# CUSensor.net
KiCad netlist of a schematic drawn in Altium Designer
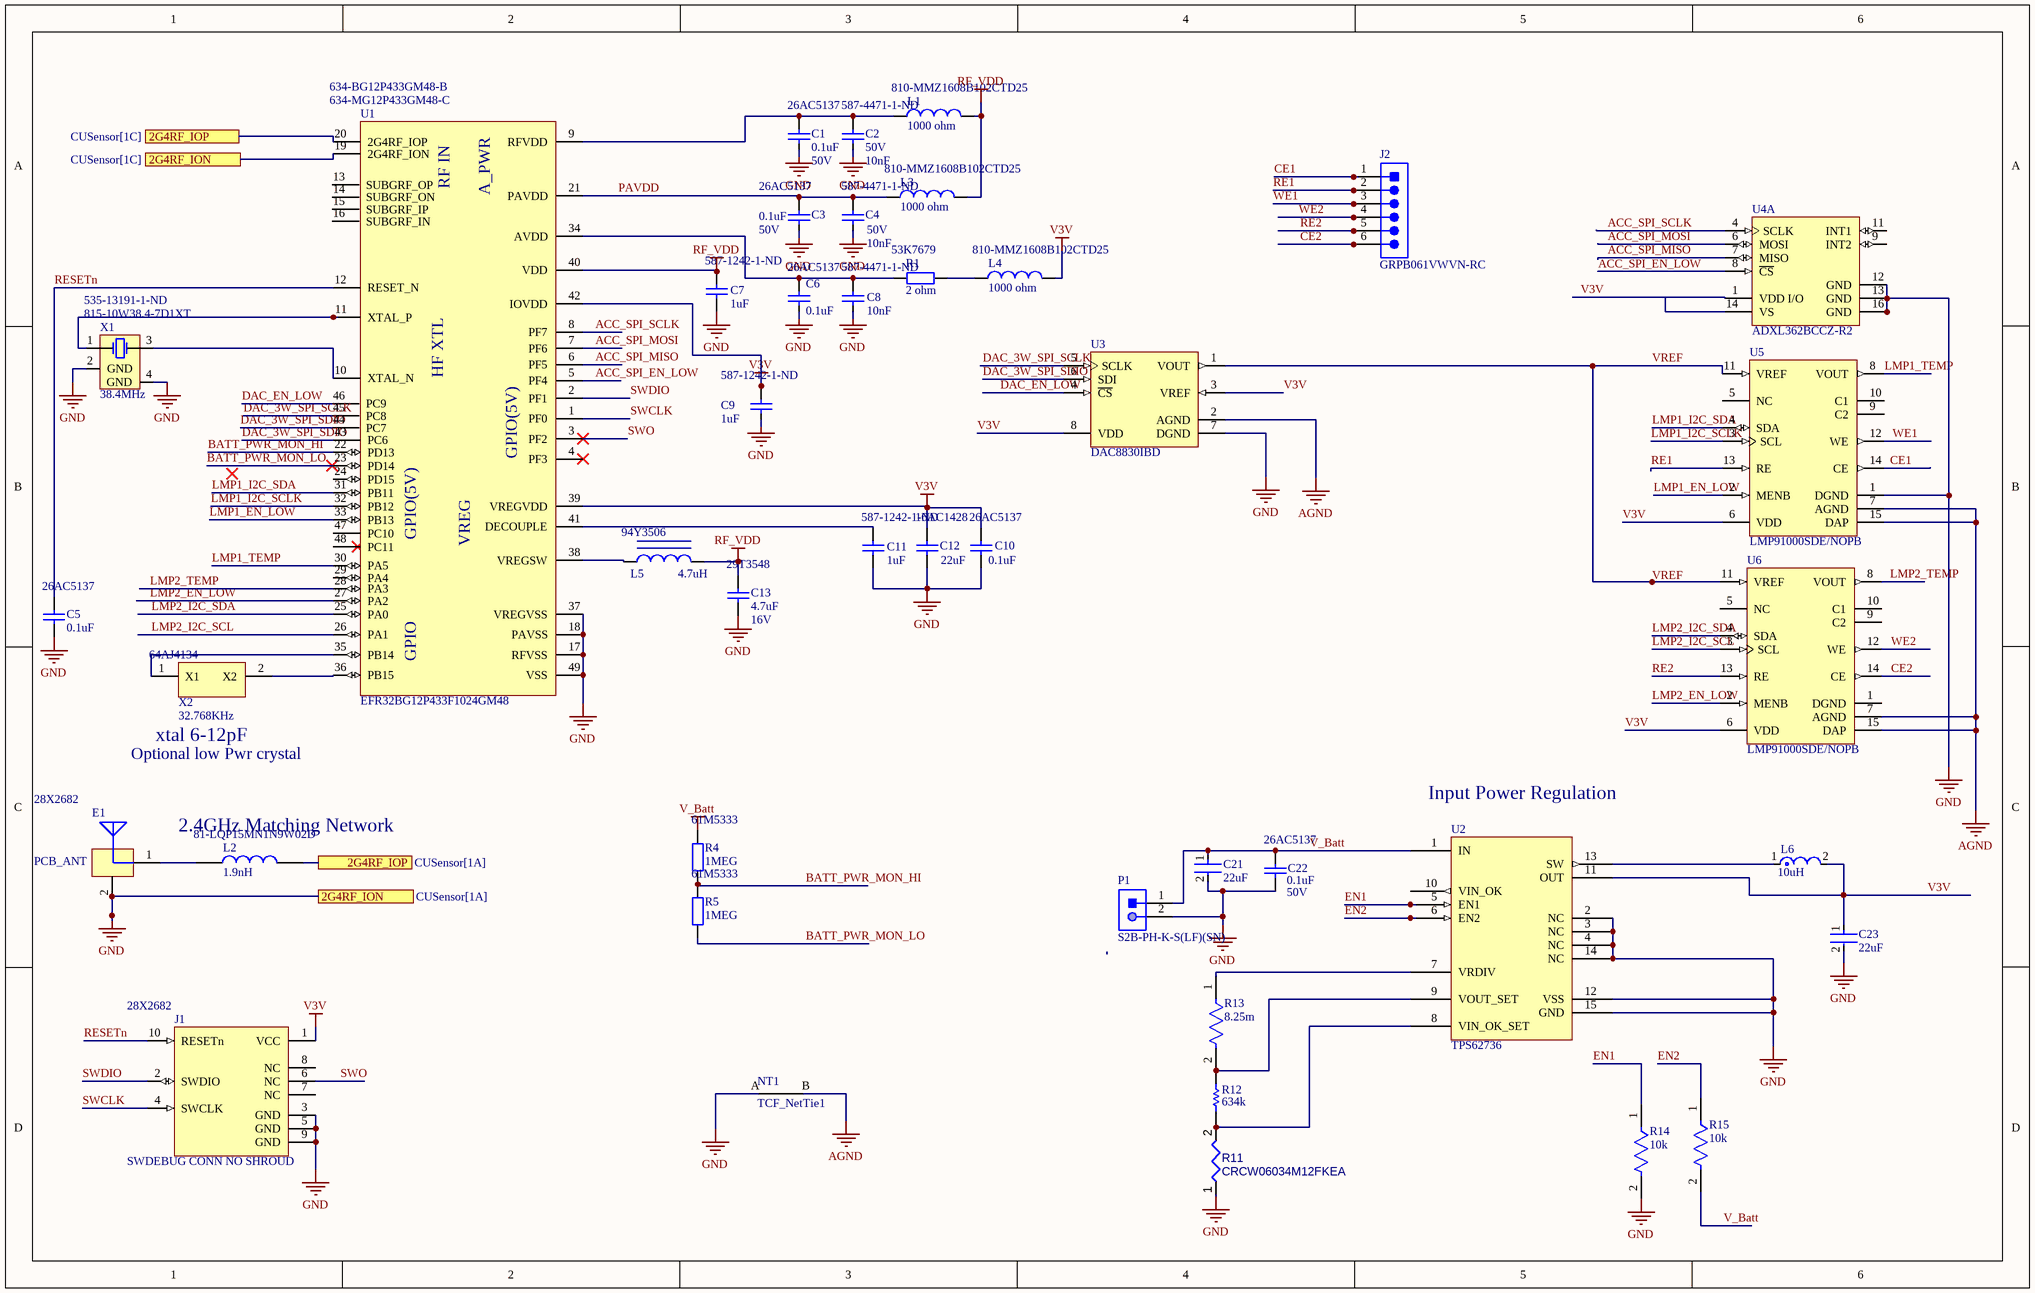
[diagram p0: CUSensor.SchDoc]

(export (version "E")
  (design (tool "Eeschema 10.0.6"))
  (components
    (comp (ref "C1")
      (value "0.1uF")
      (footprint "RESC1608N")
      (description "CAP CER .1UF 50V 10% X7R 0603")
      (fields
        (field (name "MANUFACTURER") "Murata")
        (field (name "MANUFACTURER PART#") "GRM188R71H104KA93D")
        (field (name "VOLTAGE") "50V")
        (field (name "SUPPLIER PART NUMBER 1") "26AC5137")
      )
      (libsource (lib "BCI_SCHEMATIC_LIB") (part "Cap Ceramic 0.1uF 0603_50V"))
    )
    (comp (ref "C2")
      (value "10nF")
      (footprint "RESC1608N")
      (description "CAP CER 10000PF 50V 10% X7R 0603")
      (fields
        (field (name "MANUFACTURER") "Murata")
        (field (name "MANUFACTURER PART#") "GRM188R71H103KA01D")
        (field (name "VOLTAGE") "50V")
        (field (name "SUPPLIER PART NUMBER 1") "587-4471-1-ND")
      )
      (libsource (lib "BCI_SCHEMATIC_LIB") (part "Cap Ceramic 10nF 0603"))
    )
    (comp (ref "C3")
      (value "0.1uF")
      (footprint "RESC1608N")
      (description "CAP CER .1UF 50V 10% X7R 0603")
      (fields
        (field (name "MANUFACTURER") "Murata")
        (field (name "MANUFACTURER PART#") "GRM188R71H104KA93D")
        (field (name "VOLTAGE") "50V")
        (field (name "SUPPLIER PART NUMBER 1") "26AC5137")
      )
      (libsource (lib "BCI_SCHEMATIC_LIB") (part "Cap Ceramic 0.1uF 0603_50V"))
    )
    (comp (ref "C4")
      (value "10nF")
      (footprint "RESC1608N")
      (description "CAP CER 10000PF 50V 10% X7R 0603")
      (fields
        (field (name "MANUFACTURER") "Murata")
        (field (name "MANUFACTURER PART#") "GRM188R71H103KA01D")
        (field (name "VOLTAGE") "50V")
        (field (name "SUPPLIER PART NUMBER 1") "587-4471-1-ND")
      )
      (libsource (lib "BCI_SCHEMATIC_LIB") (part "Cap Ceramic 10nF 0603"))
    )
    (comp (ref "C5")
      (value "0.1uF")
      (footprint "RESC1608N")
      (description "CAP CER .1UF 50V 10% X7R 0603")
      (fields
        (field (name "MANUFACTURER") "Murata")
        (field (name "MANUFACTURER PART#") "GRM188R71H104KA93D")
        (field (name "SUPPLIER PART NUMBER 1") "26AC5137")
      )
      (libsource (lib "BCI_SCHEMATIC_LIB") (part "Cap Ceramic 0.1uF 0603_50V"))
    )
    (comp (ref "C6")
      (value "0.1uF")
      (footprint "RESC1608N")
      (description "CAP CER .1UF 50V 10% X7R 0603")
      (fields
        (field (name "MANUFACTURER") "Murata")
        (field (name "MANUFACTURER PART#") "GRM188R71H104KA93D")
        (field (name "SUPPLIER PART NUMBER 1") "26AC5137")
      )
      (libsource (lib "BCI_SCHEMATIC_LIB") (part "Cap Ceramic 0.1uF 0603_50V"))
    )
    (comp (ref "C7")
      (value "1uF")
      (footprint "RESC1608N")
      (description "CAP CER 1UF 10V 10% X7R 0603")
      (fields
        (field (name "MANUFACTURER") "Taiyo-Yuden")
        (field (name "MANUFACTURER PART#") "LMK107B7105KA-T")
        (field (name "SUPPLIER PART NUMBER 1") "587-1242-1-ND")
      )
      (libsource (lib "BCI_SCHEMATIC_LIB") (part "Cap Ceramic 1uF_10V_ 0603"))
    )
    (comp (ref "C8")
      (value "10nF")
      (footprint "RESC1608N")
      (description "CAP CER 10000PF 50V 10% X7R 0603")
      (fields
        (field (name "MANUFACTURER") "Murata")
        (field (name "MANUFACTURER PART#") "GRM188R71H103KA01D")
        (field (name "SUPPLIER PART NUMBER 1") "587-4471-1-ND")
      )
      (libsource (lib "BCI_SCHEMATIC_LIB") (part "Cap Ceramic 10nF 0603"))
    )
    (comp (ref "C9")
      (value "1uF")
      (footprint "RESC1608N")
      (description "CAP CER 1UF 10V 10% X7R 0603")
      (fields
        (field (name "MANUFACTURER") "Taiyo-Yuden")
        (field (name "MANUFACTURER PART#") "LMK107B7105KA-T")
        (field (name "SUPPLIER PART NUMBER 1") "587-1242-1-ND")
      )
      (libsource (lib "BCI_SCHEMATIC_LIB") (part "Cap Ceramic 1uF_10V_ 0603"))
    )
    (comp (ref "C10")
      (value "0.1uF")
      (footprint "RESC1608N")
      (description "CAP CER .1UF 50V 10% X7R 0603")
      (fields
        (field (name "MANUFACTURER") "Murata")
        (field (name "MANUFACTURER PART#") "GRM188R71H104KA93D")
        (field (name "SUPPLIER PART NUMBER 1") "26AC5137")
      )
      (libsource (lib "BCI_SCHEMATIC_LIB") (part "Cap Ceramic 0.1uF 0603_50V"))
    )
    (comp (ref "C11")
      (value "1uF")
      (footprint "RESC1608N")
      (description "CAP CER 1UF 10V 10% X7R 0603")
      (fields
        (field (name "MANUFACTURER") "Taiyo-Yuden")
        (field (name "MANUFACTURER PART#") "LMK107B7105KA-T")
        (field (name "SUPPLIER PART NUMBER 1") "587-1242-1-ND")
      )
      (libsource (lib "BCI_SCHEMATIC_LIB") (part "Cap Ceramic 1uF_10V_ 0603"))
    )
    (comp (ref "C12")
      (value "22uF")
      (footprint "RESC1608N")
      (description "CAP CER 22UF 6.3V 20% X5R 0603")
      (fields
        (field (name "MANUFACTURER") "Samsung Electro-Mechanics America")
        (field (name "MANUFACTURER PART#") "CL10A226MQ8NRNE")
        (field (name "SUPPLIER PART NUMBER 1") "16AC1428")
      )
      (libsource (lib "BCI_SCHEMATIC_LIB") (part "Cap Ceramic 22uF 0603 6.3V"))
    )
    (comp (ref "C13")
      (value "4.7uF")
      (footprint "RESC1608N")
      (description "CAP CER 4.7UF 16V 10% X5R 0603")
      (fields
        (field (name "MANUFACTURER") "Taiyo Yuden")
        (field (name "MANUFACTURER PART#") "EMK107ABJ475KA-T")
        (field (name "VOLTAGE") "16V")
        (field (name "SUPPLIER PART NUMBER 1") "29T3548")
      )
      (libsource (lib "BCI_SCHEMATIC_LIB") (part "Cap Ceramic 4.7UF 16V 0603"))
    )
    (comp (ref "C21")
      (value "22uF")
      (footprint "FP-GCJ31C-0_3-IPC_B")
      (description "Cap Ceramic 22uF 10V X7R 10% Pad SMD 1206 Soft Termination  +125°C Automotive T/R")
      (libsource (lib "Altium Content Vault") (part "b4654b650e69147ec39a6b967a45e02"))
    )
    (comp (ref "C22")
      (value "0.1uF")
      (footprint "RESC1608N")
      (description "CAP CER .1UF 50V 10% X7R 0603")
      (fields
        (field (name "MANUFACTURER") "Murata")
        (field (name "MANUFACTURER PART#") "GRM188R71H104KA93D")
        (field (name "VOLTAGE") "50V")
        (field (name "SUPPLIER PART NUMBER 1") "26AC5137")
      )
      (libsource (lib "BCI_SCHEMATIC_LIB") (part "Cap Ceramic 0.1uF 0603_50V"))
    )
    (comp (ref "C23")
      (value "22uF")
      (footprint "FP-GCJ31C-0_3-IPC_B")
      (description "Cap Ceramic 22uF 10V X7R 10% Pad SMD 1206 Soft Termination  +125°C Automotive T/R")
      (libsource (lib "Altium Content Vault") (part "b4654b650e69147ec39a6b967a45e02"))
    )
    (comp (ref "E1")
      (value "PCB_ANT")
      (footprint "PCB_ANT_2.4GHz CIRCULAR")
      (description "Antenna 2.4GHz_PCB Printed")
      (fields (field (name "SUPPLIER PART NUMBER 1") "28X2682"))
      (libsource (lib "BCI_SCHEMATIC_LIB") (part "Antenna_2.4GHZ_Printed_Copper_Circular"))
    )
    (comp (ref "J1")
      (value "SWDEBUG CONN NO SHROUD")
      (footprint "CONN SMT 10 pin Dual Row - 0.050\" FCI shroudless")
      (description "CONN HEADER 10POS DL UNSHRD SMD")
      (fields
        (field (name "MANUFACTURER") "FCI")
        (field (name "DIGIKEY PART#") "609-3695-1-ND")
        (field (name "SUPPLIER PART NUMBER 1") "28X2682")
      )
      (libsource (lib "BCI_SCHEMATIC_LIB") (part "CONN JTAG SMT NO SHROUD NXP"))
    )
    (comp (ref "J2")
      (value "GRPB061VWVN-RC")
      (footprint "SLIN-GRPB061VWVN-RC_V")
      (fields (field (name "MANUFACTURER") "Sullins"))
      (libsource (lib "Altium Content Vault") (part "CN-1P-M-R6"))
    )
    (comp (ref "L1")
      (value "1000 ohm")
      (footprint "RESC1608N")
      (description "FERRITE CHIP 1000 OHM 300MA 0603")
      (fields
        (field (name "DIGIKEY PART#") "445-8672-1-ND")
        (field (name "MANUFACTURER") "TDK")
        (field (name "SUPPLIER PART NUMBER 1") "810-MMZ1608B102CTD25")
      )
      (libsource (lib "BCI_SCHEMATIC_LIB") (part "Ind Filter 0.3A_0603"))
    )
    (comp (ref "L2")
      (value "1.9nH")
      (footprint "RESC1005N")
      (fields
        (field (name "DIGIKEY PART#") "490-11739-6-ND")
        (field (name "MANUFACTURER") "Murata")
        (field (name "MANUFACTURER PART#") "LQP15MN1N9W02D")
        (field (name "SUPPLIER PART NUMBER 1") "81-LQP15MN1N9W02D")
      )
      (libsource (lib "BCI_SCHEMATIC_LIB") (part "Ind Signal 1.9nH 220mA 300mohm 0402"))
    )
    (comp (ref "L3")
      (value "1000 ohm")
      (footprint "RESC1608N")
      (description "FERRITE CHIP 1000 OHM 300MA 0603")
      (fields
        (field (name "DIGIKEY PART#") "445-8672-1-ND")
        (field (name "MANUFACTURER") "TDK")
        (field (name "SUPPLIER PART NUMBER 1") "810-MMZ1608B102CTD25")
      )
      (libsource (lib "BCI_SCHEMATIC_LIB") (part "Ind Filter 0.3A_0603"))
    )
    (comp (ref "L4")
      (value "1000 ohm")
      (footprint "RESC1608N")
      (description "FERRITE CHIP 1000 OHM 300MA 0603")
      (fields
        (field (name "DIGIKEY PART#") "445-8672-1-ND")
        (field (name "MANUFACTURER") "TDK")
        (field (name "SUPPLIER PART NUMBER 1") "810-MMZ1608B102CTD25")
      )
      (libsource (lib "BCI_SCHEMATIC_LIB") (part "Ind Filter 0.3A_0603"))
    )
    (comp (ref "L5")
      (value "4.7uH")
      (footprint "RESC2016N")
      (description "FIXED IND 4.7UH 900MA 360 MOHM")
      (fields
        (field (name "MANUFACTURER") "Bourns")
        (field (name "MANUFACTURER PART#") "SRN2010TA-4R7M")
        (field (name "SUPPLIER PART NUMBER 1") "94Y3506")
      )
      (libsource (lib "BCI_SCHEMATIC_LIB") (part "IND PWR 4.7uH 900mA 360mohm 0806"))
    )
    (comp (ref "L6")
      (value "10uH")
      (footprint "FP-LPS4018-MFG")
      (description "Shielded Power Inductors")
      (fields (field (name "TOLERANCE") "20%"))
      (libsource (lib "Altium Content Vault") (part "4cc4b267dca4c8e51f7102f422741d8"))
    )
    (comp (ref "NT1")
      (value "TCF_NetTie1")
      (footprint "TCF_NetTie1-Footprint-1")
      (description "A Net Tie")
      (libsource (lib "Altium Concord Pro on Altium 365") (part "NetTie"))
    )
    (comp (ref "P1")
      (value "S2B-PH-K-S(LF)(SN)")
      (footprint "JST-S2B-PH-K-S_V")
      (fields (field (name "TOLERANCE") "20%"))
      (libsource (lib "Altium Content Vault") (part "CN-1P-M-R2"))
    )
    (comp (ref "R1")
      (value "2 ohm")
      (footprint "RESC1608N")
      (description "RES SMD 2 OHM 1% 1/10W 0603")
      (fields
        (field (name "DIGIKEY PART#") "1276-4476-1-ND")
        (field (name "MANUFACTURER") "Samsung")
        (field (name "SUPPLIER PART NUMBER 1") "53K7679")
      )
      (libsource (lib "BCI_SCHEMATIC_LIB") (part "RES SMT 2 ohm  1% 0603"))
    )
    (comp (ref "R4")
      (value "1MEG")
      (footprint "RESC1608N")
      (description "RES SMD 1M OHM 1% 1/10W 0603")
      (fields
        (field (name "DIGIKEY PART#") "P1.00MHTR-ND")
        (field (name "MANUFACTURER") "Panasonic")
        (field (name "SUPPLIER PART NUMBER 1") "61M5333")
      )
      (libsource (lib "BCI_SCHEMATIC_LIB") (part "RES SMT 1MEG 1% 0603"))
    )
    (comp (ref "R5")
      (value "1MEG")
      (footprint "RESC1608N")
      (description "RES SMD 1M OHM 1% 1/10W 0603")
      (fields
        (field (name "DIGIKEY PART#") "P1.00MHTR-ND")
        (field (name "MANUFACTURER") "Panasonic")
        (field (name "SUPPLIER PART NUMBER 1") "61M5333")
      )
      (libsource (lib "BCI_SCHEMATIC_LIB") (part "RES SMT 1MEG 1% 0603"))
    )
    (comp (ref "R11")
      (value "CRCW06034M12FKEA")
      (footprint "RESC1608X05N")
      (description "Res Thick Film 0603 4.12M Ohm 1% 1/10W ±100ppm/°C Molded SMD SMD Paper T/R")
      (fields (field (name "MANUFACTURER") "Vishay"))
      (libsource (lib "Altium Concord Pro on Altium 365") (part "44D2KR2F"))
    )
    (comp (ref "R12")
      (value "634k")
      (footprint "RESC1609X50X30LL10T20")
      (fields (field (name "PART NUMBER") "CRCW0603634KFKEA") (field (name "MANUFACTURER") "Vishay Dale"))
      (libsource (lib "Altium Content Vault") (part "RES"))
    )
    (comp (ref "R13")
      (value "8.25m")
      (footprint "FP-CRCW0603-e3-IPC_B")
      (description "RES Thick Film, 8.25MΩ, 1%, 0.1W, 100ppm/°C, 0603")
      (fields (field (name "TOLERANCE") "1%"))
      (libsource (lib "Altium Content Vault") (part "1029c3af85768c4190bb7ad29bc67b5"))
    )
    (comp (ref "R14")
      (value "10k")
      (footprint "FP-RT0603-MFG")
      (description "RES SMD 10K OHM 0.1% 1/10W 0603")
      (fields
        (field (name "TOLERANCE") "0.001")
        (field (name "OCTOPART") "https://octopart.com/rt0603bre0710kl-yageo-1273959")
      )
      (libsource (lib "Altium Content Vault") (part "1029c3af85768c4190bb7ad29bc67b5"))
    )
    (comp (ref "R15")
      (value "10k")
      (footprint "FP-RT0603-MFG")
      (description "RES SMD 10K OHM 0.1% 1/10W 0603")
      (fields
        (field (name "TOLERANCE") "0.001")
        (field (name "OCTOPART") "https://octopart.com/rt0603bre0710kl-yageo-1273959")
      )
      (libsource (lib "Altium Content Vault") (part "1029c3af85768c4190bb7ad29bc67b5"))
    )
    (comp (ref "U1")
      (value "EFR32BG12P433F1024GM48")
      (footprint "QFN50P700X700X90_HS-49N")
      (fields
        (field (name "SUPPLIER PART NUMBER 1") "634-MG12P433GM48-C")
        (field (name "SUPPLIER PART NUMBER 2") "634-BG12P433GM48-B")
      )
      (libsource (lib "EFR32MG Series 1 BLE SubGhz QFN48") (part "EFR32BG12P433F1024GM48"))
    )
    (comp (ref "U2")
      (value "TPS62736")
      (footprint "QFN127P600-8N")
      (description "High Efficiency Nanopower Buck Converter with 50mA Load Capability")
      (libsource (lib "Altium Concord Pro on Altium 365") (part "TPS62736-Symbol-1"))
    )
    (comp (ref "U3")
      (value "DAC8830IBD")
      (footprint "TI-D8_M")
      (fields (field (name "MANUFACTURER") "Texas Instruments"))
      (libsource (lib "Altium Content Vault") (part "TI-DAC8830_EP-D8"))
    )
    (comp (ref "U4")
      (value "ADXL362BCCZ-R2")
      (footprint "ADI-CC-16-4_M")
      (fields (field (name "MANUFACTURER") "Analog Devices"))
      (libsource (lib "Altium Content Vault") (part "ADI-ADXL362-CC-16-4"))
    )
    (comp (ref "U5")
      (value "LMP91000SDE/NOPB")
      (footprint "NHL0014B_V")
      (description "Configurable AFE Potentiostat for Low-Power Chemical Sensing Applications, 14-pin LLP, 250 Reel")
      (fields (field (name "MANUFACTURER") "Texas Instruments"))
      (libsource (lib "Altium Content Vault") (part "SEN-ELECHEM-LMP91000-15"))
    )
    (comp (ref "U6")
      (value "LMP91000SDE/NOPB")
      (footprint "NHL0014B_V")
      (description "Configurable AFE Potentiostat for Low-Power Chemical Sensing Applications, 14-pin LLP, 250 Reel")
      (fields (field (name "MANUFACTURER") "Texas Instruments"))
      (libsource (lib "Altium Content Vault") (part "SEN-ELECHEM-LMP91000-15"))
    )
    (comp (ref "X1")
      (value "38.4MHz")
      (footprint "CRYSTAL SMD 2.5x2.0 ABRACON")
      (description "CRYSTAL 38.4MHZ 7pF")
      (fields
        (field (name "MANUFACTURER") "Abracon")
        (field (name "DIGIKEY PART#") "535-13784-2-ND")
        (field (name "SUPPLIER PART NUMBER 1") "815-10W38.4-7D1XT")
        (field (name "SUPPLIER PART NUMBER 2") "535-13191-1-ND")
      )
      (libsource (lib "BCI_SCHEMATIC_LIB") (part "CRYSTAL 38.4MHZ 7PF_SMD_2.5mmx2mm"))
    )
    (comp (ref "X2")
      (value "32.768KHz")
      (footprint "Crystal_SMD_3.2x1.5mm")
      (description "CRYSTAL 32.7680KHZ 12.5PF SMD")
      (fields
        (field (name "MANUFACTURER") "ECS")
        (field (name "DIGIKEY PART#") "XC1617TR-ND")
        (field (name "SUPPLIER PART NUMBER 1") "64AJ4134")
      )
      (libsource (lib "BCI_SCHEMATIC_LIB") (part "Crystal_32.768KHz 12.5pF SMD 3.2x1.5mm ECS ECS-.327-12.5-34B-TR"))
    )
  )
  (nets
    (net (code "1") (name "/2G4RF_IOP") (class "Default")
      (node (ref "L2") (pin "2") (pinfunction "2_2") (pintype "passive"))
      (node (ref "U1") (pin "20") (pinfunction "2G4RF_IOP_20") (pintype "passive"))
    )
    (net (code "2") (name "/ACC_SPI_EN_LOW") (class "Default")
      (node (ref "U1") (pin "5") (pinfunction "PF4_5") (pintype "passive"))
      (node (ref "U4") (pin "8") (pinfunction "~{CS}_8") (pintype "input"))
    )
    (net (code "3") (name "/ACC_SPI_MISO") (class "Default")
      (node (ref "U1") (pin "6") (pinfunction "PF5_6") (pintype "passive"))
      (node (ref "U4") (pin "7") (pinfunction "MISO_7") (pintype "bidirectional"))
    )
    (net (code "4") (name "/ACC_SPI_MOSI") (class "Default")
      (node (ref "U1") (pin "7") (pinfunction "PF6_7") (pintype "passive"))
      (node (ref "U4") (pin "6") (pinfunction "MOSI_6") (pintype "bidirectional"))
    )
    (net (code "5") (name "/ACC_SPI_SCLK") (class "Default")
      (node (ref "U1") (pin "8") (pinfunction "PF7_8") (pintype "passive"))
      (node (ref "U4") (pin "4") (pinfunction "SCLK_4") (pintype "input"))
    )
    (net (code "6") (name "/BATT_PWR_MON_HI") (class "Default")
      (node (ref "R4") (pin "1") (pintype "power_in"))
      (node (ref "R5") (pin "2") (pintype "power_in"))
      (node (ref "U1") (pin "22") (pinfunction "PD13_22") (pintype "bidirectional"))
    )
    (net (code "7") (name "/BATT_PWR_MON_LO") (class "Default")
      (node (ref "R5") (pin "1") (pintype "power_in"))
      (node (ref "U1") (pin "23") (pinfunction "PD14_23") (pintype "bidirectional"))
    )
    (net (code "8") (name "/CE1") (class "Default")
      (node (ref "J2") (pin "1") (pinfunction "1_1") (pintype "passive"))
      (node (ref "U5") (pin "14") (pinfunction "CE_14") (pintype "output"))
    )
    (net (code "9") (name "/CE2") (class "Default")
      (node (ref "J2") (pin "6") (pinfunction "6_6") (pintype "passive"))
      (node (ref "U6") (pin "14") (pinfunction "CE_14") (pintype "output"))
    )
    (net (code "10") (name "/DAC_3W_SPI_SCLK") (class "Default")
      (node (ref "U1") (pin "45") (pinfunction "PC8_45") (pintype "power_in"))
      (node (ref "U3") (pin "5") (pinfunction "SCLK_5") (pintype "input"))
    )
    (net (code "11") (name "/DAC_3W_SPI_SDIO") (class "Default")
      (node (ref "U1") (pin "43") (pinfunction "PC6_43") (pintype "power_in"))
      (node (ref "U1") (pin "44") (pinfunction "PC7_44") (pintype "power_in"))
      (node (ref "U3") (pin "6") (pinfunction "SDI_6") (pintype "input"))
    )
    (net (code "12") (name "/DAC_EN_LOW") (class "Default")
      (node (ref "U1") (pin "46") (pinfunction "PC9_46") (pintype "power_in"))
      (node (ref "U3") (pin "4") (pinfunction "~{CS}_4") (pintype "input"))
    )
    (net (code "13") (name "/EN1") (class "Default")
      (node (ref "R14") (pin "1") (pinfunction "1_1") (pintype "passive"))
      (node (ref "U2") (pin "5") (pinfunction "EN1_5") (pintype "input"))
    )
    (net (code "14") (name "/EN2") (class "Default")
      (node (ref "R15") (pin "1") (pinfunction "1_1") (pintype "passive"))
      (node (ref "U2") (pin "6") (pinfunction "EN2_6") (pintype "input"))
    )
    (net (code "15") (name "/LMP1_EN_LOW") (class "Default")
      (node (ref "U1") (pin "33") (pinfunction "PB13_33") (pintype "bidirectional"))
      (node (ref "U5") (pin "2") (pinfunction "MENB_2") (pintype "input"))
    )
    (net (code "16") (name "/LMP1_I2C_SCLK") (class "Default")
      (node (ref "U1") (pin "32") (pinfunction "PB12_32") (pintype "bidirectional"))
      (node (ref "U5") (pin "3") (pinfunction "SCL_3") (pintype "input"))
    )
    (net (code "17") (name "/LMP1_I2C_SDA") (class "Default")
      (node (ref "U1") (pin "31") (pinfunction "PB11_31") (pintype "bidirectional"))
      (node (ref "U5") (pin "4") (pinfunction "SDA_4") (pintype "bidirectional"))
    )
    (net (code "18") (name "/LMP1_TEMP") (class "Default")
      (node (ref "U1") (pin "30") (pinfunction "PA5_30") (pintype "bidirectional"))
      (node (ref "U5") (pin "8") (pinfunction "VOUT_8") (pintype "output"))
    )
    (net (code "19") (name "/LMP2_EN_LOW") (class "Default")
      (node (ref "U1") (pin "27") (pinfunction "PA2_27") (pintype "bidirectional"))
      (node (ref "U6") (pin "2") (pinfunction "MENB_2") (pintype "input"))
    )
    (net (code "20") (name "/LMP2_I2C_SCL") (class "Default")
      (node (ref "U1") (pin "26") (pinfunction "PA1_26") (pintype "bidirectional"))
      (node (ref "U6") (pin "3") (pinfunction "SCL_3") (pintype "input"))
    )
    (net (code "21") (name "/LMP2_I2C_SDA") (class "Default")
      (node (ref "U1") (pin "25") (pinfunction "PA0_25") (pintype "bidirectional"))
      (node (ref "U6") (pin "4") (pinfunction "SDA_4") (pintype "bidirectional"))
    )
    (net (code "22") (name "/LMP2_TEMP") (class "Default")
      (node (ref "U1") (pin "28") (pinfunction "PA3_28") (pintype "bidirectional"))
      (node (ref "U6") (pin "8") (pinfunction "VOUT_8") (pintype "output"))
    )
    (net (code "23") (name "/PAVDD") (class "Default")
      (node (ref "C3") (pin "2") (pinfunction "2_2") (pintype "passive"))
      (node (ref "C4") (pin "2") (pinfunction "2_2") (pintype "passive"))
      (node (ref "L3") (pin "1") (pinfunction "1_1") (pintype "passive"))
      (node (ref "U1") (pin "21") (pinfunction "PAVDD_21") (pintype "passive"))
    )
    (net (code "24") (name "/RE1") (class "Default")
      (node (ref "J2") (pin "2") (pinfunction "2_2") (pintype "passive"))
      (node (ref "U5") (pin "13") (pinfunction "RE_13") (pintype "input"))
    )
    (net (code "25") (name "/RE2") (class "Default")
      (node (ref "J2") (pin "5") (pinfunction "5_5") (pintype "passive"))
      (node (ref "U6") (pin "13") (pinfunction "RE_13") (pintype "input"))
    )
    (net (code "26") (name "/RESETn") (class "Default")
      (node (ref "C5") (pin "1") (pinfunction "1_1") (pintype "passive"))
      (node (ref "J1") (pin "10") (pinfunction "RESETn_10") (pintype "input"))
      (node (ref "U1") (pin "12") (pinfunction "RESET_N_12") (pintype "passive"))
    )
    (net (code "27") (name "/SWCLK") (class "Default")
      (node (ref "J1") (pin "4") (pinfunction "SWCLK_4") (pintype "input"))
      (node (ref "U1") (pin "1") (pinfunction "PF0_1") (pintype "passive"))
    )
    (net (code "28") (name "/SWDIO") (class "Default")
      (node (ref "J1") (pin "2") (pinfunction "SWDIO_2") (pintype "bidirectional"))
      (node (ref "U1") (pin "2") (pinfunction "PF1_2") (pintype "passive"))
    )
    (net (code "29") (name "/SWO") (class "Default")
      (node (ref "J1") (pin "6") (pinfunction "NC_6") (pintype "passive"))
      (node (ref "U1") (pin "3") (pinfunction "PF2_3") (pintype "passive"))
    )
    (net (code "30") (name "/VREF") (class "Default")
      (node (ref "U3") (pin "1") (pinfunction "VOUT_1") (pintype "output"))
      (node (ref "U5") (pin "11") (pinfunction "VREF_11") (pintype "input"))
      (node (ref "U6") (pin "11") (pinfunction "VREF_11") (pintype "input"))
    )
    (net (code "31") (name "/WE1") (class "Default")
      (node (ref "J2") (pin "3") (pinfunction "3_3") (pintype "passive"))
      (node (ref "U5") (pin "12") (pinfunction "WE_12") (pintype "output"))
    )
    (net (code "32") (name "/WE2") (class "Default")
      (node (ref "J2") (pin "4") (pinfunction "4_4") (pintype "passive"))
      (node (ref "U6") (pin "12") (pinfunction "WE_12") (pintype "output"))
    )
    (net (code "33") (name "AGND") (class "Default")
      (node (ref "NT1") (pin "B") (pinfunction "B_B") (pintype "passive"))
      (node (ref "U3") (pin "2") (pinfunction "AGND_2") (pintype "power_in"))
      (node (ref "U5") (pin "15") (pinfunction "DAP_15") (pintype "power_in"))
      (node (ref "U5") (pin "7") (pinfunction "AGND_7") (pintype "power_in"))
      (node (ref "U6") (pin "15") (pinfunction "DAP_15") (pintype "power_in"))
      (node (ref "U6") (pin "7") (pinfunction "AGND_7") (pintype "power_in"))
    )
    (net (code "34") (name "GND") (class "Default")
      (node (ref "C1") (pin "1") (pinfunction "1_1") (pintype "passive"))
      (node (ref "C10") (pin "1") (pinfunction "1_1") (pintype "passive"))
      (node (ref "C11") (pin "1") (pinfunction "1_1") (pintype "passive"))
      (node (ref "C12") (pin "1") (pinfunction "1_1") (pintype "passive"))
      (node (ref "C13") (pin "1") (pinfunction "1_1") (pintype "passive"))
      (node (ref "C2") (pin "1") (pinfunction "1_1") (pintype "passive"))
      (node (ref "C21") (pin "2") (pinfunction "2_2") (pintype "passive"))
      (node (ref "C22") (pin "1") (pinfunction "1_1") (pintype "passive"))
      (node (ref "C23") (pin "2") (pinfunction "2_2") (pintype "passive"))
      (node (ref "C3") (pin "1") (pinfunction "1_1") (pintype "passive"))
      (node (ref "C4") (pin "1") (pinfunction "1_1") (pintype "passive"))
      (node (ref "C5") (pin "2") (pinfunction "2_2") (pintype "passive"))
      (node (ref "C6") (pin "1") (pinfunction "1_1") (pintype "passive"))
      (node (ref "C7") (pin "1") (pinfunction "1_1") (pintype "passive"))
      (node (ref "C8") (pin "1") (pinfunction "1_1") (pintype "passive"))
      (node (ref "C9") (pin "1") (pinfunction "1_1") (pintype "passive"))
      (node (ref "E1") (pin "2") (pinfunction "GND_2") (pintype "passive"))
      (node (ref "J1") (pin "3") (pinfunction "GND_3") (pintype "passive"))
      (node (ref "J1") (pin "5") (pinfunction "GND_5") (pintype "passive"))
      (node (ref "J1") (pin "9") (pinfunction "GND_9") (pintype "passive"))
      (node (ref "NT1") (pin "A") (pinfunction "A_A") (pintype "passive"))
      (node (ref "P1") (pin "2") (pinfunction "2_2") (pintype "passive"))
      (node (ref "R11") (pin "1") (pinfunction "1_1") (pintype "passive"))
      (node (ref "R14") (pin "2") (pinfunction "2_2") (pintype "passive"))
      (node (ref "U1") (pin "17") (pinfunction "RFVSS_17") (pintype "passive"))
      (node (ref "U1") (pin "18") (pinfunction "PAVSS_18") (pintype "power_in"))
      (node (ref "U1") (pin "19") (pinfunction "2G4RF_ION_19") (pintype "passive"))
      (node (ref "U1") (pin "37") (pinfunction "VREGVSS_37") (pintype "power_in"))
      (node (ref "U1") (pin "49") (pinfunction "VSS_49") (pintype "passive"))
      (node (ref "U2") (pin "12") (pinfunction "VSS_12") (pintype "power_in"))
      (node (ref "U2") (pin "14") (pinfunction "NC_14") (pintype "passive"))
      (node (ref "U2") (pin "15") (pinfunction "GND_15") (pintype "power_in"))
      (node (ref "U2") (pin "2") (pinfunction "NC_2") (pintype "passive"))
      (node (ref "U2") (pin "3") (pinfunction "NC_3") (pintype "passive"))
      (node (ref "U2") (pin "4") (pinfunction "NC_4") (pintype "passive"))
      (node (ref "U3") (pin "7") (pinfunction "DGND_7") (pintype "power_in"))
      (node (ref "U4") (pin "12") (pinfunction "GND_12") (pintype "power_in"))
      (node (ref "U4") (pin "13") (pinfunction "GND_13") (pintype "power_in"))
      (node (ref "U4") (pin "16") (pinfunction "GND_16") (pintype "power_in"))
      (node (ref "U5") (pin "1") (pinfunction "DGND_1") (pintype "power_in"))
      (node (ref "X1") (pin "2") (pinfunction "GND_2") (pintype "passive"))
      (node (ref "X1") (pin "4") (pinfunction "GND_4") (pintype "passive"))
    )
    (net (code "35") (name "Net-(E1-SIG)") (class "Default")
      (node (ref "E1") (pin "1") (pinfunction "SIG_1") (pintype "passive"))
      (node (ref "L2") (pin "1") (pinfunction "1_1") (pintype "passive"))
    )
    (net (code "36") (name "Net-(L4-Pad1)") (class "Default")
      (node (ref "L4") (pin "1") (pinfunction "1_1") (pintype "passive"))
      (node (ref "R1") (pin "2") (pintype "power_in"))
    )
    (net (code "37") (name "Net-(U1-AVDD)") (class "Default")
      (node (ref "C6") (pin "2") (pinfunction "2_2") (pintype "passive"))
      (node (ref "C8") (pin "2") (pinfunction "2_2") (pintype "passive"))
      (node (ref "R1") (pin "1") (pintype "power_in"))
      (node (ref "U1") (pin "34") (pinfunction "AVDD_34") (pintype "power_in"))
    )
    (net (code "38") (name "Net-(U1-DECOUPLE)") (class "Default")
      (node (ref "C11") (pin "2") (pinfunction "2_2") (pintype "passive"))
      (node (ref "U1") (pin "41") (pinfunction "DECOUPLE_41") (pintype "power_in"))
    )
    (net (code "39") (name "Net-(U1-PB14)") (class "Default")
      (node (ref "U1") (pin "35") (pinfunction "PB14_35") (pintype "bidirectional"))
      (node (ref "X2") (pin "1") (pinfunction "X1_1") (pintype "passive"))
    )
    (net (code "40") (name "Net-(U1-PB15)") (class "Default")
      (node (ref "U1") (pin "36") (pinfunction "PB15_36") (pintype "bidirectional"))
      (node (ref "X2") (pin "2") (pinfunction "X2_2") (pintype "passive"))
    )
    (net (code "41") (name "Net-(U1-RFVDD)") (class "Default")
      (node (ref "C1") (pin "2") (pinfunction "2_2") (pintype "passive"))
      (node (ref "C2") (pin "2") (pinfunction "2_2") (pintype "passive"))
      (node (ref "L1") (pin "1") (pinfunction "1_1") (pintype "passive"))
      (node (ref "U1") (pin "9") (pinfunction "RFVDD_9") (pintype "passive"))
    )
    (net (code "42") (name "Net-(U1-VREGSW)") (class "Default")
      (node (ref "L5") (pin "1") (pinfunction "1_1") (pintype "passive"))
      (node (ref "U1") (pin "38") (pinfunction "VREGSW_38") (pintype "power_in"))
    )
    (net (code "43") (name "Net-(U1-XTAL_N)") (class "Default")
      (node (ref "U1") (pin "10") (pinfunction "XTAL_N_10") (pintype "passive"))
      (node (ref "X1") (pin "3") (pinfunction "OSC2_3") (pintype "passive"))
    )
    (net (code "44") (name "Net-(U1-XTAL_P)") (class "Default")
      (node (ref "U1") (pin "11") (pinfunction "XTAL_P_11") (pintype "passive"))
      (node (ref "X1") (pin "1") (pinfunction "OSC1_1") (pintype "passive"))
    )
    (net (code "45") (name "Net-(U2-SW)") (class "Default")
      (node (ref "L6") (pin "1") (pinfunction "1_1") (pintype "passive"))
      (node (ref "U2") (pin "13") (pinfunction "SW_13") (pintype "output"))
    )
    (net (code "46") (name "Net-(U2-VIN_OK_SET)") (class "Default")
      (node (ref "R11") (pin "2") (pinfunction "2_2") (pintype "passive"))
      (node (ref "R12") (pin "1") (pinfunction "1_1") (pintype "passive"))
      (node (ref "U2") (pin "8") (pinfunction "VIN_OK_SET_8") (pintype "passive"))
    )
    (net (code "47") (name "Net-(U2-VOUT_SET)") (class "Default")
      (node (ref "R12") (pin "2") (pinfunction "2_2") (pintype "passive"))
      (node (ref "R13") (pin "2") (pinfunction "2_2") (pintype "passive"))
      (node (ref "U2") (pin "9") (pinfunction "VOUT_SET_9") (pintype "passive"))
    )
    (net (code "48") (name "Net-(U2-VRDIV)") (class "Default")
      (node (ref "R13") (pin "1") (pinfunction "1_1") (pintype "passive"))
      (node (ref "U2") (pin "7") (pinfunction "VRDIV_7") (pintype "passive"))
    )
    (net (code "49") (name "RF_VDD") (class "Default")
      (node (ref "C13") (pin "2") (pinfunction "2_2") (pintype "passive"))
      (node (ref "C7") (pin "2") (pinfunction "2_2") (pintype "passive"))
      (node (ref "L1") (pin "2") (pinfunction "2_2") (pintype "passive"))
      (node (ref "L3") (pin "2") (pinfunction "2_2") (pintype "passive"))
      (node (ref "L5") (pin "2") (pinfunction "2_2") (pintype "passive"))
      (node (ref "U1") (pin "40") (pinfunction "VDD_40") (pintype "power_in"))
    )
    (net (code "50") (name "V3V") (class "Default")
      (node (ref "C10") (pin "2") (pinfunction "2_2") (pintype "passive"))
      (node (ref "C12") (pin "2") (pinfunction "2_2") (pintype "passive"))
      (node (ref "C23") (pin "1") (pinfunction "1_1") (pintype "passive"))
      (node (ref "C9") (pin "2") (pinfunction "2_2") (pintype "passive"))
      (node (ref "J1") (pin "1") (pinfunction "VCC_1") (pintype "power_in"))
      (node (ref "L4") (pin "2") (pinfunction "2_2") (pintype "passive"))
      (node (ref "L6") (pin "2") (pinfunction "2_2") (pintype "passive"))
      (node (ref "U1") (pin "39") (pinfunction "VREGVDD_39") (pintype "power_in"))
      (node (ref "U1") (pin "42") (pinfunction "IOVDD_42") (pintype "power_in"))
      (node (ref "U2") (pin "11") (pinfunction "OUT_11") (pintype "power_in"))
      (node (ref "U3") (pin "3") (pinfunction "VREF_3") (pintype "input"))
      (node (ref "U3") (pin "8") (pinfunction "VDD_8") (pintype "power_in"))
      (node (ref "U4") (pin "1") (pinfunction "VDD_I/O_1") (pintype "power_in"))
      (node (ref "U4") (pin "14") (pinfunction "VS_14") (pintype "power_in"))
      (node (ref "U5") (pin "6") (pinfunction "VDD_6") (pintype "power_in"))
      (node (ref "U6") (pin "6") (pinfunction "VDD_6") (pintype "power_in"))
    )
    (net (code "51") (name "V_Batt") (class "Default")
      (node (ref "C21") (pin "1") (pinfunction "1_1") (pintype "passive"))
      (node (ref "C22") (pin "2") (pinfunction "2_2") (pintype "passive"))
      (node (ref "P1") (pin "1") (pinfunction "1_1") (pintype "passive"))
      (node (ref "R15") (pin "2") (pinfunction "2_2") (pintype "passive"))
      (node (ref "R4") (pin "2") (pintype "power_in"))
      (node (ref "U2") (pin "1") (pinfunction "IN_1") (pintype "power_in"))
    )
    (net (code "52") (name "unconnected-(J1-NC-Pad7)") (class "Default")
      (node (ref "J1") (pin "7") (pinfunction "NC_7") (pintype "passive"))
    )
    (net (code "53") (name "unconnected-(J1-NC-Pad8)") (class "Default")
      (node (ref "J1") (pin "8") (pinfunction "NC_8") (pintype "passive"))
    )
    (net (code "54") (name "unconnected-(U1-PA4-Pad29)") (class "Default")
      (node (ref "U1") (pin "29") (pinfunction "PA4_29") (pintype "bidirectional"))
    )
    (net (code "55") (name "unconnected-(U1-PC10-Pad47)") (class "Default")
      (node (ref "U1") (pin "47") (pinfunction "PC10_47") (pintype "power_in"))
    )
    (net (code "56") (name "unconnected-(U1-PC11-Pad48)") (class "Default")
      (node (ref "U1") (pin "48") (pinfunction "PC11_48") (pintype "power_in"))
    )
    (net (code "57") (name "unconnected-(U1-PD15-Pad24)") (class "Default")
      (node (ref "U1") (pin "24") (pinfunction "PD15_24") (pintype "bidirectional"))
    )
    (net (code "58") (name "unconnected-(U1-PF3-Pad4)") (class "Default")
      (node (ref "U1") (pin "4") (pinfunction "PF3_4") (pintype "passive+no_connect"))
    )
    (net (code "59") (name "unconnected-(U1-SUBGRF_IN-Pad16)") (class "Default")
      (node (ref "U1") (pin "16") (pinfunction "SUBGRF_IN_16") (pintype "passive"))
    )
    (net (code "60") (name "unconnected-(U1-SUBGRF_IP-Pad15)") (class "Default")
      (node (ref "U1") (pin "15") (pinfunction "SUBGRF_IP_15") (pintype "passive"))
    )
    (net (code "61") (name "unconnected-(U1-SUBGRF_ON-Pad14)") (class "Default")
      (node (ref "U1") (pin "14") (pinfunction "SUBGRF_ON_14") (pintype "passive"))
    )
    (net (code "62") (name "unconnected-(U1-SUBGRF_OP-Pad13)") (class "Default")
      (node (ref "U1") (pin "13") (pinfunction "SUBGRF_OP_13") (pintype "passive"))
    )
    (net (code "63") (name "unconnected-(U2-VIN_OK-Pad10)") (class "Default")
      (node (ref "U2") (pin "10") (pinfunction "VIN_OK_10") (pintype "output"))
    )
    (net (code "64") (name "unconnected-(U4A-INT1-Pad11)") (class "Default")
      (node (ref "U4") (pin "11") (pinfunction "INT1_11") (pintype "bidirectional"))
    )
    (net (code "65") (name "unconnected-(U4A-INT2-Pad9)") (class "Default")
      (node (ref "U4") (pin "9") (pinfunction "INT2_9") (pintype "bidirectional"))
    )
    (net (code "66") (name "unconnected-(U5-C1-Pad10)") (class "Default")
      (node (ref "U5") (pin "10") (pinfunction "C1_10") (pintype "passive"))
    )
    (net (code "67") (name "unconnected-(U5-C2-Pad9)") (class "Default")
      (node (ref "U5") (pin "9") (pinfunction "C2_9") (pintype "passive"))
    )
    (net (code "68") (name "unconnected-(U5-NC-Pad5)") (class "Default")
      (node (ref "U5") (pin "5") (pinfunction "NC_5") (pintype "passive"))
    )
    (net (code "69") (name "unconnected-(U6-C1-Pad10)") (class "Default")
      (node (ref "U6") (pin "10") (pinfunction "C1_10") (pintype "passive"))
    )
    (net (code "70") (name "unconnected-(U6-C2-Pad9)") (class "Default")
      (node (ref "U6") (pin "9") (pinfunction "C2_9") (pintype "passive"))
    )
    (net (code "71") (name "unconnected-(U6-DGND-Pad1)") (class "Default")
      (node (ref "U6") (pin "1") (pinfunction "DGND_1") (pintype "power_in"))
    )
    (net (code "72") (name "unconnected-(U6-NC-Pad5)") (class "Default")
      (node (ref "U6") (pin "5") (pinfunction "NC_5") (pintype "passive"))
    )
  )
)
